# Dual_filter_common_mode_and_differential.net
KiCad netlist of a schematic drawn in EAGLE
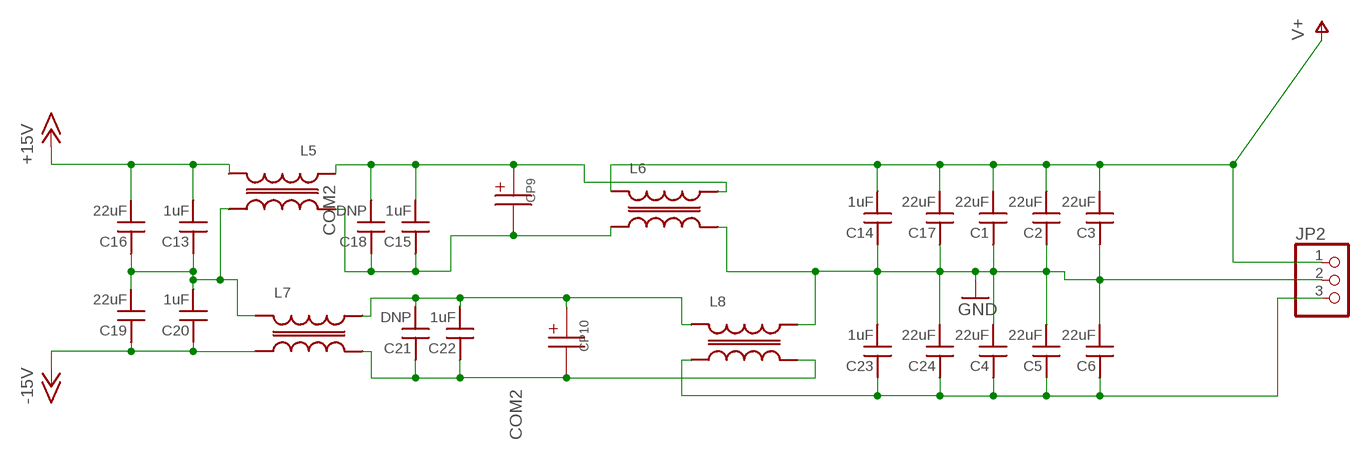
[diagram p0: schematic, sheet 1]

(export (version "E")
  (design (tool "Eeschema 10.0.6"))
  (components
    (comp (ref "C1")
      (value "22uF")
      (footprint "eagle-import:C_MLCC_0805")
      (libsource (lib "eagle-import") (part "C_MLCC_SMDCMLCC_0805"))
    )
    (comp (ref "C2")
      (value "22uF")
      (footprint "eagle-import:C_MLCC_0805")
      (libsource (lib "eagle-import") (part "C_MLCC_SMDCMLCC_0805"))
    )
    (comp (ref "C3")
      (value "22uF")
      (footprint "eagle-import:C_MLCC_0805")
      (libsource (lib "eagle-import") (part "C_MLCC_SMDCMLCC_0805"))
    )
    (comp (ref "C4")
      (value "22uF")
      (footprint "eagle-import:C_MLCC_0805")
      (libsource (lib "eagle-import") (part "C_MLCC_SMDCMLCC_0805"))
    )
    (comp (ref "C5")
      (value "22uF")
      (footprint "eagle-import:C_MLCC_0805")
      (libsource (lib "eagle-import") (part "C_MLCC_SMDCMLCC_0805"))
    )
    (comp (ref "C6")
      (value "22uF")
      (footprint "eagle-import:C_MLCC_0805")
      (libsource (lib "eagle-import") (part "C_MLCC_SMDCMLCC_0805"))
    )
    (comp (ref "C13")
      (value "1uF")
      (footprint "eagle-import:C_MLCC_0805")
      (libsource (lib "eagle-import") (part "C_MLCC_SMDCMLCC_0805"))
    )
    (comp (ref "C14")
      (value "1uF")
      (footprint "eagle-import:C_MLCC_0805")
      (libsource (lib "eagle-import") (part "C_MLCC_SMDCMLCC_0805"))
    )
    (comp (ref "C15")
      (value "1uF")
      (footprint "eagle-import:C_MLCC_0805")
      (libsource (lib "eagle-import") (part "C_MLCC_SMDCMLCC_0805"))
    )
    (comp (ref "C16")
      (value "22uF")
      (footprint "eagle-import:C_MLCC_0805")
      (libsource (lib "eagle-import") (part "C_MLCC_SMDCMLCC_0805"))
    )
    (comp (ref "C17")
      (value "22uF")
      (footprint "eagle-import:C_MLCC_0805")
      (libsource (lib "eagle-import") (part "C_MLCC_SMDCMLCC_0805"))
    )
    (comp (ref "C18")
      (value "DNP")
      (footprint "eagle-import:C_MLCC_0805")
      (libsource (lib "eagle-import") (part "C_MLCC_SMDCMLCC_0805"))
    )
    (comp (ref "C19")
      (value "22uF")
      (footprint "eagle-import:C_MLCC_0805")
      (libsource (lib "eagle-import") (part "C_MLCC_SMDCMLCC_0805"))
    )
    (comp (ref "C20")
      (value "1uF")
      (footprint "eagle-import:C_MLCC_0805")
      (libsource (lib "eagle-import") (part "C_MLCC_SMDCMLCC_0805"))
    )
    (comp (ref "C21")
      (value "DNP")
      (footprint "eagle-import:C_MLCC_0805")
      (libsource (lib "eagle-import") (part "C_MLCC_SMDCMLCC_0805"))
    )
    (comp (ref "C22")
      (value "1uF")
      (footprint "eagle-import:C_MLCC_0805")
      (libsource (lib "eagle-import") (part "C_MLCC_SMDCMLCC_0805"))
    )
    (comp (ref "C23")
      (value "1uF")
      (footprint "eagle-import:C_MLCC_0805")
      (libsource (lib "eagle-import") (part "C_MLCC_SMDCMLCC_0805"))
    )
    (comp (ref "C24")
      (value "22uF")
      (footprint "eagle-import:C_MLCC_0805")
      (libsource (lib "eagle-import") (part "C_MLCC_SMDCMLCC_0805"))
    )
    (comp (ref "CP9")
      (value "CAP-POLPANASONIC_F")
      (footprint "eagle-import:PANASONIC_F")
      (libsource (lib "eagle-import") (part "CAP-POLPANASONIC_F"))
    )
    (comp (ref "CP10")
      (value "CAP-POLPANASONIC_F")
      (footprint "eagle-import:PANASONIC_F")
      (libsource (lib "eagle-import") (part "CAP-POLPANASONIC_F"))
    )
    (comp (ref "JP2")
      (value "PINHD-1X3")
      (footprint "eagle-import:1X03")
      (libsource (lib "eagle-import") (part "PINHD-1X3"))
    )
    (comp (ref "L5")
      (value "MSD7342")
      (footprint "eagle-import:MSD7342")
      (libsource (lib "eagle-import") (part "MSD7342"))
    )
    (comp (ref "L6")
      (value "MSD7342")
      (footprint "eagle-import:MSD7342")
      (libsource (lib "eagle-import") (part "MSD7342"))
    )
    (comp (ref "L7")
      (value "MSD7342")
      (footprint "eagle-import:MSD7342")
      (libsource (lib "eagle-import") (part "MSD7342"))
    )
    (comp (ref "L8")
      (value "MSD7342")
      (footprint "eagle-import:MSD7342")
      (libsource (lib "eagle-import") (part "MSD7342"))
    )
  )
  (nets
    (net (code "1") (name "+15V") (class "Default")
      (node (ref "C13") (pin "P$2") (pinfunction "2_P$2") (pintype "passive"))
      (node (ref "C16") (pin "P$2") (pinfunction "2_P$2") (pintype "passive"))
      (node (ref "L5") (pin "4") (pinfunction "4_4") (pintype "passive"))
    )
    (net (code "2") (name "-15V") (class "Default")
      (node (ref "C19") (pin "P$1") (pinfunction "1_P$1") (pintype "passive"))
      (node (ref "C20") (pin "P$1") (pinfunction "1_P$1") (pintype "passive"))
      (node (ref "L7") (pin "1") (pinfunction "1_1") (pintype "passive"))
    )
    (net (code "3") (name "/COM2") (class "Default")
      (node (ref "C13") (pin "P$1") (pinfunction "1_P$1") (pintype "passive"))
      (node (ref "C16") (pin "P$1") (pinfunction "1_P$1") (pintype "passive"))
      (node (ref "C19") (pin "P$2") (pinfunction "2_P$2") (pintype "passive"))
      (node (ref "C20") (pin "P$2") (pinfunction "2_P$2") (pintype "passive"))
      (node (ref "L5") (pin "3") (pinfunction "3_3") (pintype "passive"))
      (node (ref "L7") (pin "2") (pinfunction "2_2") (pintype "passive"))
    )
    (net (code "4") (name "GND") (class "Default")
      (node (ref "C1") (pin "P$1") (pinfunction "1_P$1") (pintype "passive"))
      (node (ref "C14") (pin "P$1") (pinfunction "1_P$1") (pintype "passive"))
      (node (ref "C17") (pin "P$1") (pinfunction "1_P$1") (pintype "passive"))
      (node (ref "C2") (pin "P$1") (pinfunction "1_P$1") (pintype "passive"))
      (node (ref "C23") (pin "P$2") (pinfunction "2_P$2") (pintype "passive"))
      (node (ref "C24") (pin "P$2") (pinfunction "2_P$2") (pintype "passive"))
      (node (ref "C3") (pin "P$1") (pinfunction "1_P$1") (pintype "passive"))
      (node (ref "C4") (pin "P$2") (pinfunction "2_P$2") (pintype "passive"))
      (node (ref "C5") (pin "P$2") (pinfunction "2_P$2") (pintype "passive"))
      (node (ref "C6") (pin "P$2") (pinfunction "2_P$2") (pintype "passive"))
      (node (ref "JP2") (pin "2") (pinfunction "2_2") (pintype "passive"))
      (node (ref "L6") (pin "3") (pinfunction "3_3") (pintype "passive"))
      (node (ref "L8") (pin "4") (pinfunction "4_4") (pintype "passive"))
    )
    (net (code "5") (name "Net-(C15-1)") (class "Default")
      (node (ref "C15") (pin "P$1") (pinfunction "1_P$1") (pintype "passive"))
      (node (ref "C18") (pin "P$1") (pinfunction "1_P$1") (pintype "passive"))
      (node (ref "CP9") (pin "-") (pinfunction "P$2_-") (pintype "passive"))
      (node (ref "L5") (pin "1") (pinfunction "1_1") (pintype "passive"))
      (node (ref "L6") (pin "1") (pinfunction "1_1") (pintype "passive"))
    )
    (net (code "6") (name "Net-(C15-2)") (class "Default")
      (node (ref "C15") (pin "P$2") (pinfunction "2_P$2") (pintype "passive"))
      (node (ref "C18") (pin "P$2") (pinfunction "2_P$2") (pintype "passive"))
      (node (ref "CP9") (pin "+") (pinfunction "P$1_+") (pintype "passive"))
      (node (ref "L5") (pin "2") (pinfunction "2_2") (pintype "passive"))
      (node (ref "L6") (pin "4") (pinfunction "4_4") (pintype "passive"))
    )
    (net (code "7") (name "Net-(C21-1)") (class "Default")
      (node (ref "C21") (pin "P$1") (pinfunction "1_P$1") (pintype "passive"))
      (node (ref "C22") (pin "P$1") (pinfunction "1_P$1") (pintype "passive"))
      (node (ref "CP10") (pin "-") (pinfunction "P$2_-") (pintype "passive"))
      (node (ref "L7") (pin "3") (pinfunction "3_3") (pintype "passive"))
      (node (ref "L8") (pin "3") (pinfunction "3_3") (pintype "passive"))
    )
    (net (code "8") (name "Net-(C21-2)") (class "Default")
      (node (ref "C21") (pin "P$2") (pinfunction "2_P$2") (pintype "passive"))
      (node (ref "C22") (pin "P$2") (pinfunction "2_P$2") (pintype "passive"))
      (node (ref "CP10") (pin "+") (pinfunction "P$1_+") (pintype "passive"))
      (node (ref "L7") (pin "4") (pinfunction "4_4") (pintype "passive"))
      (node (ref "L8") (pin "2") (pinfunction "2_2") (pintype "passive"))
    )
    (net (code "9") (name "Net-(C23-1)") (class "Default")
      (node (ref "C23") (pin "P$1") (pinfunction "1_P$1") (pintype "passive"))
      (node (ref "C24") (pin "P$1") (pinfunction "1_P$1") (pintype "passive"))
      (node (ref "C4") (pin "P$1") (pinfunction "1_P$1") (pintype "passive"))
      (node (ref "C5") (pin "P$1") (pinfunction "1_P$1") (pintype "passive"))
      (node (ref "C6") (pin "P$1") (pinfunction "1_P$1") (pintype "passive"))
      (node (ref "JP2") (pin "3") (pinfunction "3_3") (pintype "passive"))
      (node (ref "L8") (pin "1") (pinfunction "1_1") (pintype "passive"))
    )
    (net (code "10") (name "V+") (class "Default")
      (node (ref "C1") (pin "P$2") (pinfunction "2_P$2") (pintype "passive"))
      (node (ref "C14") (pin "P$2") (pinfunction "2_P$2") (pintype "passive"))
      (node (ref "C17") (pin "P$2") (pinfunction "2_P$2") (pintype "passive"))
      (node (ref "C2") (pin "P$2") (pinfunction "2_P$2") (pintype "passive"))
      (node (ref "C3") (pin "P$2") (pinfunction "2_P$2") (pintype "passive"))
      (node (ref "JP2") (pin "1") (pinfunction "1_1") (pintype "passive"))
      (node (ref "L6") (pin "2") (pinfunction "2_2") (pintype "passive"))
    )
  )
)
